# xmega_revC.net
KiCad netlist of a schematic drawn in EAGLE
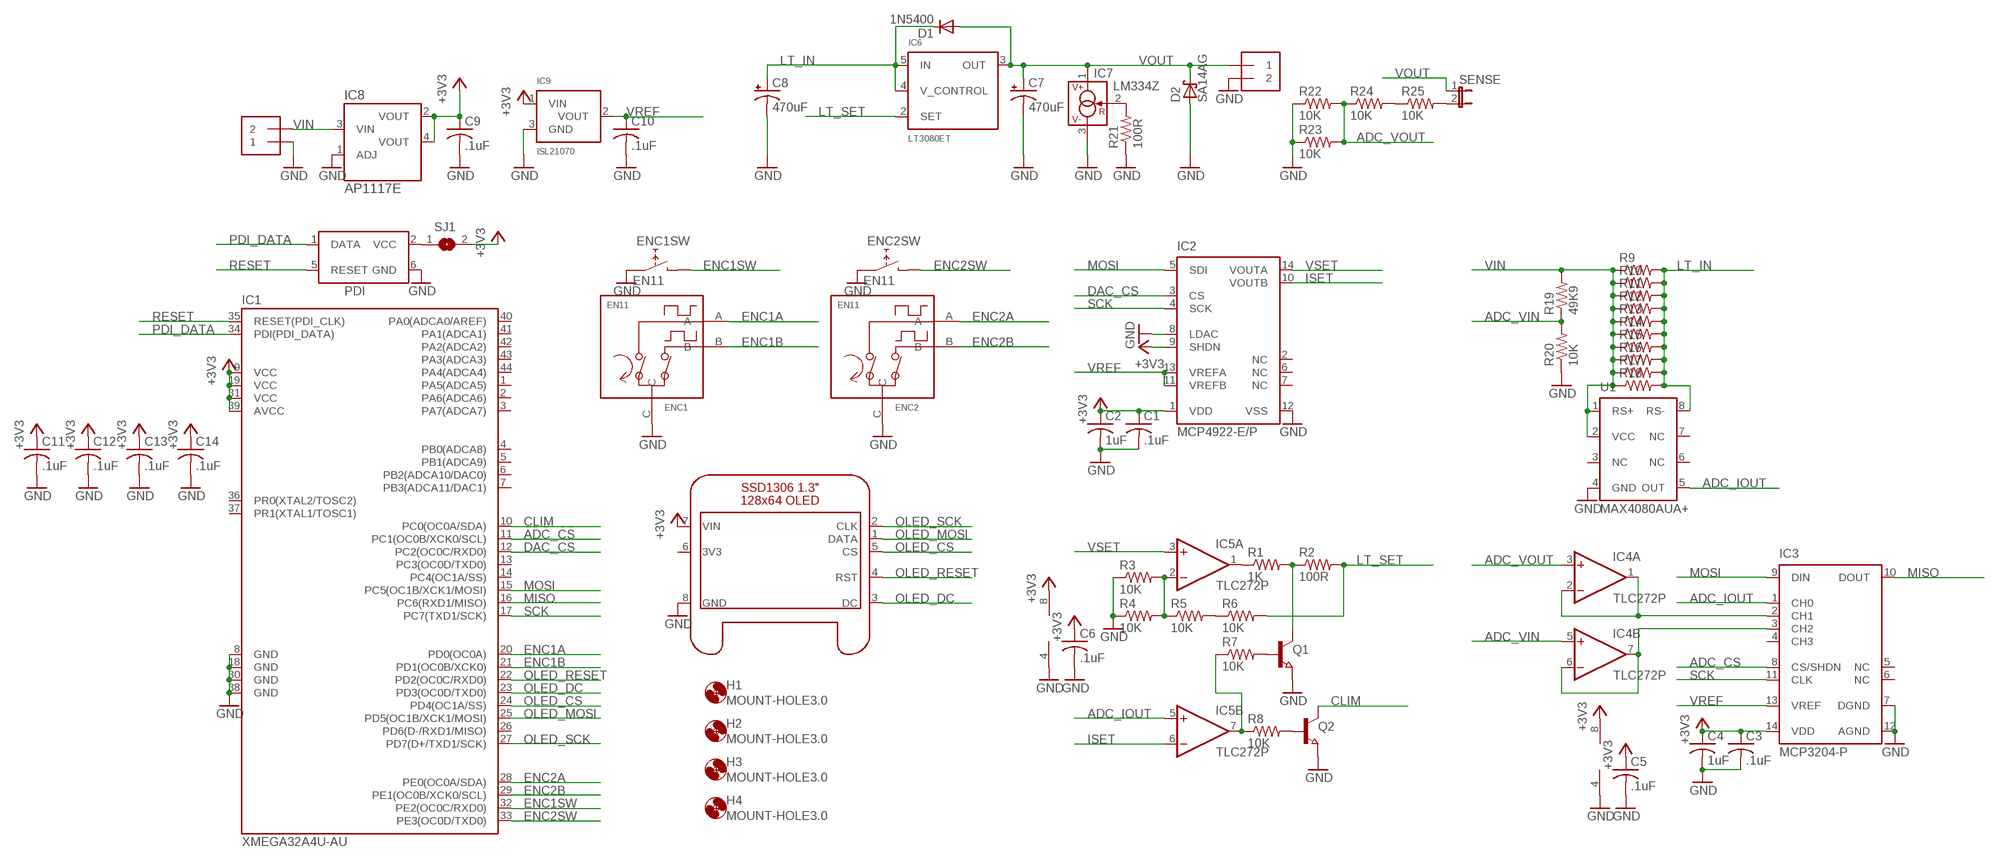
[diagram p0: schematic, sheet 1]

(export (version "E")
  (design (tool "Eeschema 10.0.6"))
  (components
    (comp (ref "C1")
      (value ".1uF")
      (footprint "eagle-import:C050-024X044")
      (libsource (lib "eagle-import") (part "C-US050-024X044"))
    )
    (comp (ref "C2")
      (value "1uF")
      (footprint "eagle-import:C050-024X044")
      (libsource (lib "eagle-import") (part "C-US050-024X044"))
    )
    (comp (ref "C3")
      (value ".1uF")
      (footprint "eagle-import:C050-024X044")
      (libsource (lib "eagle-import") (part "C-US050-024X044"))
    )
    (comp (ref "C4")
      (value "1uF")
      (footprint "eagle-import:C050-024X044")
      (libsource (lib "eagle-import") (part "C-US050-024X044"))
    )
    (comp (ref "C5")
      (value ".1uF")
      (footprint "eagle-import:C050-024X044")
      (libsource (lib "eagle-import") (part "C-US050-024X044"))
    )
    (comp (ref "C6")
      (value ".1uF")
      (footprint "eagle-import:C050-024X044")
      (libsource (lib "eagle-import") (part "C-US050-024X044"))
    )
    (comp (ref "C7")
      (value "470uF")
      (footprint "eagle-import:E5-10,5")
      (libsource (lib "eagle-import") (part "CPOL-USE5-10.5"))
    )
    (comp (ref "C8")
      (value "470uF")
      (footprint "eagle-import:E5-10,5")
      (libsource (lib "eagle-import") (part "CPOL-USE5-10.5"))
    )
    (comp (ref "C9")
      (value ".1uF")
      (footprint "eagle-import:C050-024X044")
      (libsource (lib "eagle-import") (part "C-US050-024X044"))
    )
    (comp (ref "C10")
      (value ".1uF")
      (footprint "eagle-import:C050-024X044")
      (libsource (lib "eagle-import") (part "C-US050-024X044"))
    )
    (comp (ref "C11")
      (value ".1uF")
      (footprint "eagle-import:C0805K")
      (libsource (lib "eagle-import") (part "C-USC0805K"))
    )
    (comp (ref "C12")
      (value ".1uF")
      (footprint "eagle-import:C0805K")
      (libsource (lib "eagle-import") (part "C-USC0805K"))
    )
    (comp (ref "C13")
      (value ".1uF")
      (footprint "eagle-import:C0805K")
      (libsource (lib "eagle-import") (part "C-USC0805K"))
    )
    (comp (ref "C14")
      (value ".1uF")
      (footprint "eagle-import:C0805K")
      (libsource (lib "eagle-import") (part "C-USC0805K"))
    )
    (comp (ref "D1")
      (value "1N5400")
      (footprint "eagle-import:DO201-15")
      (libsource (lib "eagle-import") (part "1N5400"))
    )
    (comp (ref "D2")
      (value "SA14AG")
      (footprint "eagle-import:DO41-7")
      (libsource (lib "eagle-import") (part "SCHOTTKY-DIODEDO41-7"))
    )
    (comp (ref "ENC1")
      (value "EN11")
      (footprint "eagle-import:EN11-VS_")
      (libsource (lib "eagle-import") (part "EN11"))
    )
    (comp (ref "ENC2")
      (value "EN11")
      (footprint "eagle-import:EN11-VS_")
      (libsource (lib "eagle-import") (part "EN11"))
    )
    (comp (ref "H1")
      (value "MOUNT-HOLE3.0")
      (footprint "eagle-import:3,0")
      (libsource (lib "eagle-import") (part "MOUNT-HOLE3.0"))
    )
    (comp (ref "H2")
      (value "MOUNT-HOLE3.0")
      (footprint "eagle-import:3,0")
      (libsource (lib "eagle-import") (part "MOUNT-HOLE3.0"))
    )
    (comp (ref "H3")
      (value "MOUNT-HOLE3.0")
      (footprint "eagle-import:3,0")
      (libsource (lib "eagle-import") (part "MOUNT-HOLE3.0"))
    )
    (comp (ref "H4")
      (value "MOUNT-HOLE3.0")
      (footprint "eagle-import:3,0")
      (libsource (lib "eagle-import") (part "MOUNT-HOLE3.0"))
    )
    (comp (ref "IC1")
      (value "XMEGA32A4U-AU")
      (footprint "eagle-import:TQFP44")
      (libsource (lib "eagle-import") (part "XMEGA32A4U-AU"))
    )
    (comp (ref "IC2")
      (value "MCP4922-E/P")
      (footprint "eagle-import:DIL14")
      (libsource (lib "eagle-import") (part "MCP4922-E/P"))
    )
    (comp (ref "IC3")
      (value "MCP3204-P")
      (footprint "eagle-import:DIL14")
      (libsource (lib "eagle-import") (part "MCP3204-P"))
    )
    (comp (ref "IC4")
      (value "TLC272P")
      (footprint "eagle-import:DIL08")
      (libsource (lib "eagle-import") (part "TLC272P"))
    )
    (comp (ref "IC5")
      (value "TLC272P")
      (footprint "eagle-import:DIL08")
      (libsource (lib "eagle-import") (part "TLC272P"))
    )
    (comp (ref "IC6")
      (value "LT3080ET")
      (footprint "eagle-import:TO220-51")
      (libsource (lib "eagle-import") (part "LT3080ET"))
    )
    (comp (ref "IC7")
      (value "LM334Z")
      (footprint "eagle-import:TO92")
      (libsource (lib "eagle-import") (part "LM34Z3"))
    )
    (comp (ref "IC8")
      (value "AP1117E")
      (footprint "eagle-import:SOT223-3")
      (libsource (lib "eagle-import") (part "AP1117E"))
    )
    (comp (ref "IC9")
      (value "ISL21070")
      (footprint "eagle-import:SOT-23")
      (libsource (lib "eagle-import") (part "ISL21070"))
    )
    (comp (ref "OLED1")
      (value "128X64_OLED")
      (footprint "eagle-import:128X64_OLED")
      (libsource (lib "eagle-import") (part "128X64_OLED"))
    )
    (comp (ref "OUT")
      (value "1X2-3.5MM")
      (footprint "eagle-import:1X2-3.5MM")
      (libsource (lib "eagle-import") (part "1X2-3.5MM"))
    )
    (comp (ref "PDI")
      (value "XMEGAPDI")
      (footprint "eagle-import:AVRISP")
      (libsource (lib "eagle-import") (part "XMEGAPDI"))
    )
    (comp (ref "Q1")
      (value "NPN-TRANSISTOR_SOT23")
      (footprint "eagle-import:SOT23")
      (libsource (lib "eagle-import") (part "NPN-TRANSISTOR_SOT23"))
    )
    (comp (ref "Q2")
      (value "NPN-TRANSISTOR_SOT23")
      (footprint "eagle-import:SOT23")
      (libsource (lib "eagle-import") (part "NPN-TRANSISTOR_SOT23"))
    )
    (comp (ref "R1")
      (value "1K")
      (footprint "eagle-import:R0805")
      (libsource (lib "eagle-import") (part "R-US_R0805"))
    )
    (comp (ref "R2")
      (value "100R")
      (footprint "eagle-import:R0805")
      (libsource (lib "eagle-import") (part "R-US_R0805"))
    )
    (comp (ref "R3")
      (value "10K")
      (footprint "eagle-import:R0805")
      (libsource (lib "eagle-import") (part "R-US_R0805"))
    )
    (comp (ref "R4")
      (value "10K")
      (footprint "eagle-import:R0805")
      (libsource (lib "eagle-import") (part "R-US_R0805"))
    )
    (comp (ref "R5")
      (value "10K")
      (footprint "eagle-import:R0805")
      (libsource (lib "eagle-import") (part "R-US_R0805"))
    )
    (comp (ref "R6")
      (value "10K")
      (footprint "eagle-import:R0805")
      (libsource (lib "eagle-import") (part "R-US_R0805"))
    )
    (comp (ref "R7")
      (value "10K")
      (footprint "eagle-import:R0805")
      (libsource (lib "eagle-import") (part "R-US_R0805"))
    )
    (comp (ref "R8")
      (value "10K")
      (footprint "eagle-import:R0805")
      (libsource (lib "eagle-import") (part "R-US_R0805"))
    )
    (comp (ref "R9")
      (value "R-US_0207/10")
      (footprint "eagle-import:0207_10")
      (libsource (lib "eagle-import") (part "R-US_0207/10"))
    )
    (comp (ref "R10")
      (value "R-US_0207/10")
      (footprint "eagle-import:0207_10")
      (libsource (lib "eagle-import") (part "R-US_0207/10"))
    )
    (comp (ref "R11")
      (value "R-US_0207/10")
      (footprint "eagle-import:0207_10")
      (libsource (lib "eagle-import") (part "R-US_0207/10"))
    )
    (comp (ref "R12")
      (value "R-US_0207/10")
      (footprint "eagle-import:0207_10")
      (libsource (lib "eagle-import") (part "R-US_0207/10"))
    )
    (comp (ref "R13")
      (value "R-US_0207/10")
      (footprint "eagle-import:0207_10")
      (libsource (lib "eagle-import") (part "R-US_0207/10"))
    )
    (comp (ref "R14")
      (value "R-US_0207/10")
      (footprint "eagle-import:0207_10")
      (libsource (lib "eagle-import") (part "R-US_0207/10"))
    )
    (comp (ref "R15")
      (value "R-US_0207/10")
      (footprint "eagle-import:0207_10")
      (libsource (lib "eagle-import") (part "R-US_0207/10"))
    )
    (comp (ref "R16")
      (value "R-US_0207/10")
      (footprint "eagle-import:0207_10")
      (libsource (lib "eagle-import") (part "R-US_0207/10"))
    )
    (comp (ref "R17")
      (value "R-US_0207/10")
      (footprint "eagle-import:0207_10")
      (libsource (lib "eagle-import") (part "R-US_0207/10"))
    )
    (comp (ref "R18")
      (value "R-US_0207/10")
      (footprint "eagle-import:0207_10")
      (libsource (lib "eagle-import") (part "R-US_0207/10"))
    )
    (comp (ref "R19")
      (value "49K9")
      (footprint "eagle-import:R0805")
      (libsource (lib "eagle-import") (part "R-US_R0805"))
    )
    (comp (ref "R20")
      (value "10K")
      (footprint "eagle-import:R0805")
      (libsource (lib "eagle-import") (part "R-US_R0805"))
    )
    (comp (ref "R21")
      (value "100R")
      (footprint "eagle-import:R0805")
      (libsource (lib "eagle-import") (part "R-US_R0805"))
    )
    (comp (ref "R22")
      (value "10K")
      (footprint "eagle-import:R0805")
      (libsource (lib "eagle-import") (part "R-US_R0805"))
    )
    (comp (ref "R23")
      (value "10K")
      (footprint "eagle-import:R0805")
      (libsource (lib "eagle-import") (part "R-US_R0805"))
    )
    (comp (ref "R24")
      (value "10K")
      (footprint "eagle-import:R0805")
      (libsource (lib "eagle-import") (part "R-US_R0805"))
    )
    (comp (ref "R25")
      (value "10K")
      (footprint "eagle-import:R0805")
      (libsource (lib "eagle-import") (part "R-US_R0805"))
    )
    (comp (ref "SENSE")
      (value "JP1E")
      (footprint "eagle-import:JP1")
      (libsource (lib "eagle-import") (part "JP1E"))
    )
    (comp (ref "SJ1") (value "SJ") (footprint "eagle-import:SJ") (libsource (lib "eagle-import") (part "SJ")))
    (comp (ref "U1")
      (value "MAX4080AUA+")
      (footprint "eagle-import:SO08")
      (libsource (lib "eagle-import") (part "MAX4080AUA+"))
    )
    (comp (ref "VIN")
      (value "1X2-3.5MM")
      (footprint "eagle-import:1X2-3.5MM")
      (libsource (lib "eagle-import") (part "1X2-3.5MM"))
    )
  )
  (nets
    (net (code "1") (name "+3V3") (class "Default")
      (node (ref "C1") (pin "1") (pinfunction "1_1") (pintype "passive"))
      (node (ref "C11") (pin "1") (pinfunction "1_1") (pintype "passive"))
      (node (ref "C12") (pin "1") (pinfunction "1_1") (pintype "passive"))
      (node (ref "C13") (pin "1") (pinfunction "1_1") (pintype "passive"))
      (node (ref "C14") (pin "1") (pinfunction "1_1") (pintype "passive"))
      (node (ref "C2") (pin "1") (pinfunction "1_1") (pintype "passive"))
      (node (ref "C3") (pin "1") (pinfunction "1_1") (pintype "passive"))
      (node (ref "C4") (pin "1") (pinfunction "1_1") (pintype "passive"))
      (node (ref "C5") (pin "1") (pinfunction "1_1") (pintype "passive"))
      (node (ref "C6") (pin "1") (pinfunction "1_1") (pintype "passive"))
      (node (ref "C9") (pin "1") (pinfunction "1_1") (pintype "passive"))
      (node (ref "IC1") (pin "19") (pinfunction "VCC_19") (pintype "power_in"))
      (node (ref "IC1") (pin "31") (pinfunction "VCC_31") (pintype "power_in"))
      (node (ref "IC1") (pin "39") (pinfunction "AVCC_39") (pintype "power_in"))
      (node (ref "IC1") (pin "9") (pinfunction "VCC_9") (pintype "power_in"))
      (node (ref "IC2") (pin "1") (pinfunction "VDD_1") (pintype "bidirectional"))
      (node (ref "IC2") (pin "9") (pinfunction "SHDN_9") (pintype "bidirectional"))
      (node (ref "IC3") (pin "14") (pinfunction "VDD_14") (pintype "bidirectional"))
      (node (ref "IC4") (pin "8") (pinfunction "V+_8") (pintype "power_in"))
      (node (ref "IC5") (pin "8") (pinfunction "V+_8") (pintype "power_in"))
      (node (ref "IC8") (pin "2") (pinfunction "VOUT_2") (pintype "bidirectional"))
      (node (ref "IC8") (pin "4") (pinfunction "VOUT_4") (pintype "bidirectional"))
      (node (ref "IC9") (pin "1") (pinfunction "VIN_1") (pintype "bidirectional"))
      (node (ref "OLED1") (pin "7") (pinfunction "VIN_7") (pintype "power_in"))
      (node (ref "SJ1") (pin "2") (pinfunction "2_2") (pintype "passive"))
    )
    (net (code "2") (name "/3V3") (class "Default")
      (node (ref "OLED1") (pin "6") (pinfunction "3V3_6") (pintype "power_in"))
    )
    (net (code "3") (name "/ADC_CS") (class "Default")
      (node (ref "IC1") (pin "11") (pinfunction "PC1(OC0B/XCK0/SCL)_11") (pintype "bidirectional"))
      (node (ref "IC3") (pin "8") (pinfunction "CS/SHDN_8") (pintype "bidirectional"))
    )
    (net (code "4") (name "/ADC_IOUT") (class "Default")
      (node (ref "IC3") (pin "1") (pinfunction "CH0_1") (pintype "bidirectional"))
      (node (ref "IC5") (pin "5") (pinfunction "+IN_5") (pintype "input"))
      (node (ref "U1") (pin "5") (pinfunction "OUT_5") (pintype "bidirectional"))
    )
    (net (code "5") (name "/ADC_VIN") (class "Default")
      (node (ref "IC4") (pin "5") (pinfunction "+IN_5") (pintype "input"))
      (node (ref "R19") (pin "1") (pinfunction "1_1") (pintype "passive"))
      (node (ref "R20") (pin "2") (pinfunction "2_2") (pintype "passive"))
    )
    (net (code "6") (name "/ADC_VOUT") (class "Default")
      (node (ref "IC4") (pin "3") (pinfunction "+IN_3") (pintype "input"))
      (node (ref "R22") (pin "2") (pinfunction "2_2") (pintype "passive"))
      (node (ref "R23") (pin "2") (pinfunction "2_2") (pintype "passive"))
      (node (ref "R24") (pin "1") (pinfunction "1_1") (pintype "passive"))
    )
    (net (code "7") (name "/CLIM") (class "Default")
      (node (ref "IC1") (pin "10") (pinfunction "PC0(OC0A/SDA)_10") (pintype "bidirectional"))
      (node (ref "Q2") (pin "3") (pinfunction "C_3") (pintype "passive"))
    )
    (net (code "8") (name "/DAC_CS") (class "Default")
      (node (ref "IC1") (pin "12") (pinfunction "PC2(OC0C/RXD0)_12") (pintype "bidirectional"))
      (node (ref "IC2") (pin "3") (pinfunction "CS_3") (pintype "bidirectional"))
    )
    (net (code "9") (name "/ENC1A") (class "Default")
      (node (ref "ENC1") (pin "A") (pinfunction "A_A") (pintype "bidirectional"))
      (node (ref "IC1") (pin "20") (pinfunction "PD0(OC0A)_20") (pintype "bidirectional"))
    )
    (net (code "10") (name "/ENC1B") (class "Default")
      (node (ref "ENC1") (pin "B") (pinfunction "B_B") (pintype "bidirectional"))
      (node (ref "IC1") (pin "21") (pinfunction "PD1(OC0B/XCK0)_21") (pintype "bidirectional"))
    )
    (net (code "11") (name "/ENC1SW") (class "Default")
      (node (ref "ENC1") (pin "E") (pinfunction "E_E") (pintype "passive"))
      (node (ref "IC1") (pin "32") (pinfunction "PE2(OC0C/RXD0)_32") (pintype "bidirectional"))
    )
    (net (code "12") (name "/ENC2A") (class "Default")
      (node (ref "ENC2") (pin "A") (pinfunction "A_A") (pintype "bidirectional"))
      (node (ref "IC1") (pin "28") (pinfunction "PE0(OC0A/SDA)_28") (pintype "bidirectional"))
    )
    (net (code "13") (name "/ENC2B") (class "Default")
      (node (ref "ENC2") (pin "B") (pinfunction "B_B") (pintype "bidirectional"))
      (node (ref "IC1") (pin "29") (pinfunction "PE1(OC0B/XCK0/SCL)_29") (pintype "bidirectional"))
    )
    (net (code "14") (name "/ENC2SW") (class "Default")
      (node (ref "ENC2") (pin "E") (pinfunction "E_E") (pintype "passive"))
      (node (ref "IC1") (pin "33") (pinfunction "PE3(OC0D/TXD0)_33") (pintype "bidirectional"))
    )
    (net (code "15") (name "/ISET") (class "Default")
      (node (ref "IC2") (pin "10") (pinfunction "VOUTB_10") (pintype "bidirectional"))
      (node (ref "IC5") (pin "6") (pinfunction "-IN_6") (pintype "input"))
    )
    (net (code "16") (name "/LT_IN") (class "Default")
      (node (ref "C8") (pin "+") (pinfunction "+_+") (pintype "passive"))
      (node (ref "D1") (pin "C") (pinfunction "C_C") (pintype "passive"))
      (node (ref "IC6") (pin "4") (pinfunction "V_CONTROL_4") (pintype "bidirectional"))
      (node (ref "IC6") (pin "5") (pinfunction "IN_5") (pintype "bidirectional"))
      (node (ref "R10") (pin "2") (pinfunction "2_2") (pintype "passive"))
      (node (ref "R11") (pin "2") (pinfunction "2_2") (pintype "passive"))
      (node (ref "R12") (pin "2") (pinfunction "2_2") (pintype "passive"))
      (node (ref "R13") (pin "2") (pinfunction "2_2") (pintype "passive"))
      (node (ref "R14") (pin "2") (pinfunction "2_2") (pintype "passive"))
      (node (ref "R15") (pin "2") (pinfunction "2_2") (pintype "passive"))
      (node (ref "R16") (pin "2") (pinfunction "2_2") (pintype "passive"))
      (node (ref "R17") (pin "2") (pinfunction "2_2") (pintype "passive"))
      (node (ref "R18") (pin "2") (pinfunction "2_2") (pintype "passive"))
      (node (ref "R9") (pin "2") (pinfunction "2_2") (pintype "passive"))
      (node (ref "U1") (pin "8") (pinfunction "RS-_8") (pintype "bidirectional"))
    )
    (net (code "17") (name "/LT_SET") (class "Default")
      (node (ref "IC6") (pin "2") (pinfunction "SET_2") (pintype "bidirectional"))
      (node (ref "R2") (pin "2") (pinfunction "2_2") (pintype "passive"))
      (node (ref "R6") (pin "2") (pinfunction "2_2") (pintype "passive"))
    )
    (net (code "18") (name "/MISO") (class "Default")
      (node (ref "IC1") (pin "16") (pinfunction "PC6(RXD1/MISO)_16") (pintype "bidirectional"))
      (node (ref "IC3") (pin "10") (pinfunction "DOUT_10") (pintype "bidirectional"))
    )
    (net (code "19") (name "/MOSI") (class "Default")
      (node (ref "IC1") (pin "15") (pinfunction "PC5(OC1B/XCK1/MOSI)_15") (pintype "bidirectional"))
      (node (ref "IC2") (pin "5") (pinfunction "SDI_5") (pintype "bidirectional"))
      (node (ref "IC3") (pin "9") (pinfunction "DIN_9") (pintype "bidirectional"))
    )
    (net (code "20") (name "/OLED_CS") (class "Default")
      (node (ref "IC1") (pin "24") (pinfunction "PD4(OC1A/SS)_24") (pintype "bidirectional"))
      (node (ref "OLED1") (pin "5") (pinfunction "CS_5") (pintype "input"))
    )
    (net (code "21") (name "/OLED_DC") (class "Default")
      (node (ref "IC1") (pin "23") (pinfunction "PD3(OC0D/TXD0)_23") (pintype "bidirectional"))
      (node (ref "OLED1") (pin "3") (pinfunction "DC_3") (pintype "input"))
    )
    (net (code "22") (name "/OLED_MOSI") (class "Default")
      (node (ref "IC1") (pin "25") (pinfunction "PD5(OC1B/XCK1/MOSI)_25") (pintype "bidirectional"))
      (node (ref "OLED1") (pin "1") (pinfunction "DATA_1") (pintype "input"))
    )
    (net (code "23") (name "/OLED_RESET") (class "Default")
      (node (ref "IC1") (pin "22") (pinfunction "PD2(OC0C/RXD0)_22") (pintype "bidirectional"))
      (node (ref "OLED1") (pin "4") (pinfunction "RST_4") (pintype "input"))
    )
    (net (code "24") (name "/OLED_SCK") (class "Default")
      (node (ref "IC1") (pin "27") (pinfunction "PD7(D+/TXD1/SCK)_27") (pintype "bidirectional"))
      (node (ref "OLED1") (pin "2") (pinfunction "CLK_2") (pintype "input"))
    )
    (net (code "25") (name "/PDI_DATA") (class "Default")
      (node (ref "IC1") (pin "34") (pinfunction "PDI(PDI_DATA)_34") (pintype "bidirectional"))
      (node (ref "PDI") (pin "1") (pinfunction "DATA_1") (pintype "input"))
    )
    (net (code "26") (name "/RESET") (class "Default")
      (node (ref "IC1") (pin "35") (pinfunction "RESET(PDI_CLK)_35") (pintype "input"))
      (node (ref "PDI") (pin "5") (pinfunction "RESET_5") (pintype "output"))
    )
    (net (code "27") (name "/SCK") (class "Default")
      (node (ref "IC1") (pin "17") (pinfunction "PC7(TXD1/SCK)_17") (pintype "bidirectional"))
      (node (ref "IC2") (pin "4") (pinfunction "SCK_4") (pintype "bidirectional"))
      (node (ref "IC3") (pin "11") (pinfunction "CLK_11") (pintype "bidirectional"))
    )
    (net (code "28") (name "/VIN") (class "Default")
      (node (ref "IC8") (pin "3") (pinfunction "VIN_3") (pintype "bidirectional"))
      (node (ref "R10") (pin "1") (pinfunction "1_1") (pintype "passive"))
      (node (ref "R11") (pin "1") (pinfunction "1_1") (pintype "passive"))
      (node (ref "R12") (pin "1") (pinfunction "1_1") (pintype "passive"))
      (node (ref "R13") (pin "1") (pinfunction "1_1") (pintype "passive"))
      (node (ref "R14") (pin "1") (pinfunction "1_1") (pintype "passive"))
      (node (ref "R15") (pin "1") (pinfunction "1_1") (pintype "passive"))
      (node (ref "R16") (pin "1") (pinfunction "1_1") (pintype "passive"))
      (node (ref "R17") (pin "1") (pinfunction "1_1") (pintype "passive"))
      (node (ref "R18") (pin "1") (pinfunction "1_1") (pintype "passive"))
      (node (ref "R19") (pin "2") (pinfunction "2_2") (pintype "passive"))
      (node (ref "R9") (pin "1") (pinfunction "1_1") (pintype "passive"))
      (node (ref "U1") (pin "1") (pinfunction "RS+_1") (pintype "bidirectional"))
      (node (ref "U1") (pin "2") (pinfunction "VCC_2") (pintype "bidirectional"))
      (node (ref "VIN") (pin "2") (pinfunction "2_2") (pintype "passive"))
    )
    (net (code "29") (name "/VOUT") (class "Default")
      (node (ref "C7") (pin "+") (pinfunction "+_+") (pintype "passive"))
      (node (ref "D1") (pin "A") (pinfunction "A_A") (pintype "passive"))
      (node (ref "D2") (pin "C") (pinfunction "C_C") (pintype "passive"))
      (node (ref "IC6") (pin "3") (pinfunction "OUT_3") (pintype "bidirectional"))
      (node (ref "IC7") (pin "1") (pinfunction "V+_1") (pintype "passive"))
      (node (ref "OUT") (pin "1") (pinfunction "1_1") (pintype "passive"))
      (node (ref "SENSE") (pin "1") (pinfunction "1_1") (pintype "passive"))
    )
    (net (code "30") (name "/VREF") (class "Default")
      (node (ref "C10") (pin "1") (pinfunction "1_1") (pintype "passive"))
      (node (ref "IC2") (pin "11") (pinfunction "VREFB_11") (pintype "bidirectional"))
      (node (ref "IC2") (pin "13") (pinfunction "VREFA_13") (pintype "bidirectional"))
      (node (ref "IC3") (pin "13") (pinfunction "VREF_13") (pintype "bidirectional"))
      (node (ref "IC9") (pin "2") (pinfunction "VOUT_2") (pintype "bidirectional"))
    )
    (net (code "31") (name "/VSET") (class "Default")
      (node (ref "IC2") (pin "14") (pinfunction "VOUTA_14") (pintype "bidirectional"))
      (node (ref "IC5") (pin "3") (pinfunction "+IN_3") (pintype "input"))
    )
    (net (code "32") (name "GND") (class "Default")
      (node (ref "C1") (pin "2") (pinfunction "2_2") (pintype "passive"))
      (node (ref "C10") (pin "2") (pinfunction "2_2") (pintype "passive"))
      (node (ref "C11") (pin "2") (pinfunction "2_2") (pintype "passive"))
      (node (ref "C12") (pin "2") (pinfunction "2_2") (pintype "passive"))
      (node (ref "C13") (pin "2") (pinfunction "2_2") (pintype "passive"))
      (node (ref "C14") (pin "2") (pinfunction "2_2") (pintype "passive"))
      (node (ref "C2") (pin "2") (pinfunction "2_2") (pintype "passive"))
      (node (ref "C3") (pin "2") (pinfunction "2_2") (pintype "passive"))
      (node (ref "C4") (pin "2") (pinfunction "2_2") (pintype "passive"))
      (node (ref "C5") (pin "2") (pinfunction "2_2") (pintype "passive"))
      (node (ref "C6") (pin "2") (pinfunction "2_2") (pintype "passive"))
      (node (ref "C7") (pin "-") (pinfunction "-_-") (pintype "passive"))
      (node (ref "C8") (pin "-") (pinfunction "-_-") (pintype "passive"))
      (node (ref "C9") (pin "2") (pinfunction "2_2") (pintype "passive"))
      (node (ref "D2") (pin "A") (pinfunction "A_A") (pintype "passive"))
      (node (ref "ENC1") (pin "C") (pinfunction "C_C") (pintype "bidirectional"))
      (node (ref "ENC1") (pin "D") (pinfunction "D_D") (pintype "passive"))
      (node (ref "ENC2") (pin "C") (pinfunction "C_C") (pintype "bidirectional"))
      (node (ref "ENC2") (pin "D") (pinfunction "D_D") (pintype "passive"))
      (node (ref "IC1") (pin "18") (pinfunction "GND_18") (pintype "power_in"))
      (node (ref "IC1") (pin "30") (pinfunction "GND_30") (pintype "power_in"))
      (node (ref "IC1") (pin "38") (pinfunction "GND_38") (pintype "power_in"))
      (node (ref "IC1") (pin "8") (pinfunction "GND_8") (pintype "power_in"))
      (node (ref "IC2") (pin "12") (pinfunction "VSS_12") (pintype "bidirectional"))
      (node (ref "IC2") (pin "8") (pinfunction "LDAC_8") (pintype "bidirectional"))
      (node (ref "IC3") (pin "12") (pinfunction "AGND_12") (pintype "bidirectional"))
      (node (ref "IC3") (pin "7") (pinfunction "DGND_7") (pintype "bidirectional"))
      (node (ref "IC4") (pin "4") (pinfunction "V-_4") (pintype "power_in"))
      (node (ref "IC5") (pin "4") (pinfunction "V-_4") (pintype "power_in"))
      (node (ref "IC7") (pin "3") (pinfunction "V-_3") (pintype "passive"))
      (node (ref "IC8") (pin "1") (pinfunction "ADJ_1") (pintype "bidirectional"))
      (node (ref "IC9") (pin "3") (pinfunction "GND_3") (pintype "bidirectional"))
      (node (ref "OLED1") (pin "8") (pinfunction "GND_8") (pintype "power_in"))
      (node (ref "OUT") (pin "2") (pinfunction "2_2") (pintype "passive"))
      (node (ref "PDI") (pin "6") (pinfunction "GND_6") (pintype "power_in"))
      (node (ref "Q1") (pin "2") (pinfunction "E_2") (pintype "passive"))
      (node (ref "Q2") (pin "2") (pinfunction "E_2") (pintype "passive"))
      (node (ref "R20") (pin "1") (pinfunction "1_1") (pintype "passive"))
      (node (ref "R21") (pin "1") (pinfunction "1_1") (pintype "passive"))
      (node (ref "R22") (pin "1") (pinfunction "1_1") (pintype "passive"))
      (node (ref "R23") (pin "1") (pinfunction "1_1") (pintype "passive"))
      (node (ref "R3") (pin "1") (pinfunction "1_1") (pintype "passive"))
      (node (ref "R4") (pin "1") (pinfunction "1_1") (pintype "passive"))
      (node (ref "U1") (pin "4") (pinfunction "GND_4") (pintype "bidirectional"))
      (node (ref "VIN") (pin "1") (pinfunction "1_1") (pintype "passive"))
    )
    (net (code "33") (name "Net-(IC3-CH1)") (class "Default")
      (node (ref "IC3") (pin "2") (pinfunction "CH1_2") (pintype "bidirectional"))
      (node (ref "IC4") (pin "1") (pinfunction "OUT_1") (pintype "output"))
      (node (ref "IC4") (pin "2") (pinfunction "-IN_2") (pintype "input"))
    )
    (net (code "34") (name "Net-(IC3-CH2)") (class "Default")
      (node (ref "IC3") (pin "3") (pinfunction "CH2_3") (pintype "bidirectional"))
      (node (ref "IC4") (pin "6") (pinfunction "-IN_6") (pintype "input"))
      (node (ref "IC4") (pin "7") (pinfunction "OUT_7") (pintype "output"))
    )
    (net (code "35") (name "Net-(IC5A--IN)") (class "Default")
      (node (ref "IC5") (pin "2") (pinfunction "-IN_2") (pintype "input"))
      (node (ref "R3") (pin "2") (pinfunction "2_2") (pintype "passive"))
      (node (ref "R4") (pin "2") (pinfunction "2_2") (pintype "passive"))
      (node (ref "R5") (pin "1") (pinfunction "1_1") (pintype "passive"))
    )
    (net (code "36") (name "Net-(IC5A-OUT)") (class "Default")
      (node (ref "IC5") (pin "1") (pinfunction "OUT_1") (pintype "output"))
      (node (ref "R1") (pin "1") (pinfunction "1_1") (pintype "passive"))
    )
    (net (code "37") (name "Net-(IC5B-OUT)") (class "Default")
      (node (ref "IC5") (pin "7") (pinfunction "OUT_7") (pintype "output"))
      (node (ref "R7") (pin "1") (pinfunction "1_1") (pintype "passive"))
      (node (ref "R8") (pin "1") (pinfunction "1_1") (pintype "passive"))
    )
    (net (code "38") (name "Net-(IC7-R)") (class "Default")
      (node (ref "IC7") (pin "2") (pinfunction "R_2") (pintype "passive"))
      (node (ref "R21") (pin "2") (pinfunction "2_2") (pintype "passive"))
    )
    (net (code "39") (name "Net-(PDI-VCC)") (class "Default")
      (node (ref "PDI") (pin "2") (pinfunction "VCC_2") (pintype "power_in"))
      (node (ref "SJ1") (pin "1") (pinfunction "1_1") (pintype "passive"))
    )
    (net (code "40") (name "Net-(Q1-B)") (class "Default")
      (node (ref "Q1") (pin "1") (pinfunction "B_1") (pintype "passive"))
      (node (ref "R7") (pin "2") (pinfunction "2_2") (pintype "passive"))
    )
    (net (code "41") (name "Net-(Q1-C)") (class "Default")
      (node (ref "Q1") (pin "3") (pinfunction "C_3") (pintype "passive"))
      (node (ref "R1") (pin "2") (pinfunction "2_2") (pintype "passive"))
      (node (ref "R2") (pin "1") (pinfunction "1_1") (pintype "passive"))
    )
    (net (code "42") (name "Net-(Q2-B)") (class "Default")
      (node (ref "Q2") (pin "1") (pinfunction "B_1") (pintype "passive"))
      (node (ref "R8") (pin "2") (pinfunction "2_2") (pintype "passive"))
    )
    (net (code "43") (name "Net-(R5-Pad2)") (class "Default")
      (node (ref "R5") (pin "2") (pinfunction "2_2") (pintype "passive"))
      (node (ref "R6") (pin "1") (pinfunction "1_1") (pintype "passive"))
    )
    (net (code "44") (name "Net-(R24-Pad2)") (class "Default")
      (node (ref "R24") (pin "2") (pinfunction "2_2") (pintype "passive"))
      (node (ref "R25") (pin "1") (pinfunction "1_1") (pintype "passive"))
    )
    (net (code "45") (name "Net-(R25-Pad2)") (class "Default")
      (node (ref "R25") (pin "2") (pinfunction "2_2") (pintype "passive"))
      (node (ref "SENSE") (pin "2") (pinfunction "2_2") (pintype "passive"))
    )
    (net (code "46") (name "unconnected-(IC1-PA0(ADCA0{slash}AREF)-Pad40)") (class "Default")
      (node (ref "IC1") (pin "40") (pinfunction "PA0(ADCA0/AREF)_40") (pintype "bidirectional"))
    )
    (net (code "47") (name "unconnected-(IC1-PA1(ADCA1)-Pad41)") (class "Default")
      (node (ref "IC1") (pin "41") (pinfunction "PA1(ADCA1)_41") (pintype "bidirectional"))
    )
    (net (code "48") (name "unconnected-(IC1-PA2(ADCA2)-Pad42)") (class "Default")
      (node (ref "IC1") (pin "42") (pinfunction "PA2(ADCA2)_42") (pintype "bidirectional"))
    )
    (net (code "49") (name "unconnected-(IC1-PA3(ADCA3)-Pad43)") (class "Default")
      (node (ref "IC1") (pin "43") (pinfunction "PA3(ADCA3)_43") (pintype "bidirectional"))
    )
    (net (code "50") (name "unconnected-(IC1-PA4(ADCA4)-Pad44)") (class "Default")
      (node (ref "IC1") (pin "44") (pinfunction "PA4(ADCA4)_44") (pintype "bidirectional"))
    )
    (net (code "51") (name "unconnected-(IC1-PA5(ADCA5)-Pad1)") (class "Default")
      (node (ref "IC1") (pin "1") (pinfunction "PA5(ADCA5)_1") (pintype "bidirectional"))
    )
    (net (code "52") (name "unconnected-(IC1-PA6(ADCA6)-Pad2)") (class "Default")
      (node (ref "IC1") (pin "2") (pinfunction "PA6(ADCA6)_2") (pintype "bidirectional"))
    )
    (net (code "53") (name "unconnected-(IC1-PA7(ADCA7)-Pad3)") (class "Default")
      (node (ref "IC1") (pin "3") (pinfunction "PA7(ADCA7)_3") (pintype "bidirectional"))
    )
    (net (code "54") (name "unconnected-(IC1-PB0(ADCA8)-Pad4)") (class "Default")
      (node (ref "IC1") (pin "4") (pinfunction "PB0(ADCA8)_4") (pintype "bidirectional"))
    )
    (net (code "55") (name "unconnected-(IC1-PB1(ADCA9)-Pad5)") (class "Default")
      (node (ref "IC1") (pin "5") (pinfunction "PB1(ADCA9)_5") (pintype "bidirectional"))
    )
    (net (code "56") (name "unconnected-(IC1-PB2(ADCA10{slash}DAC0)-Pad6)") (class "Default")
      (node (ref "IC1") (pin "6") (pinfunction "PB2(ADCA10/DAC0)_6") (pintype "bidirectional"))
    )
    (net (code "57") (name "unconnected-(IC1-PB3(ADCA11{slash}DAC1)-Pad7)") (class "Default")
      (node (ref "IC1") (pin "7") (pinfunction "PB3(ADCA11/DAC1)_7") (pintype "bidirectional"))
    )
    (net (code "58") (name "unconnected-(IC1-PC3(OC0D{slash}TXD0)-Pad13)") (class "Default")
      (node (ref "IC1") (pin "13") (pinfunction "PC3(OC0D/TXD0)_13") (pintype "bidirectional"))
    )
    (net (code "59") (name "unconnected-(IC1-PC4(OC1A{slash}SS)-Pad14)") (class "Default")
      (node (ref "IC1") (pin "14") (pinfunction "PC4(OC1A/SS)_14") (pintype "bidirectional"))
    )
    (net (code "60") (name "unconnected-(IC1-PD6(D-{slash}RXD1{slash}MISO)-Pad26)") (class "Default")
      (node (ref "IC1") (pin "26") (pinfunction "PD6(D-/RXD1/MISO)_26") (pintype "bidirectional"))
    )
    (net (code "61") (name "unconnected-(IC1-PR0(XTAL2{slash}TOSC2)-Pad36)") (class "Default")
      (node (ref "IC1") (pin "36") (pinfunction "PR0(XTAL2/TOSC2)_36") (pintype "bidirectional"))
    )
    (net (code "62") (name "unconnected-(IC1-PR1(XTAL1{slash}TOSC1)-Pad37)") (class "Default")
      (node (ref "IC1") (pin "37") (pinfunction "PR1(XTAL1/TOSC1)_37") (pintype "bidirectional"))
    )
    (net (code "63") (name "unconnected-(IC2-NC-Pad2)") (class "Default")
      (node (ref "IC2") (pin "2") (pinfunction "NC_2") (pintype "bidirectional"))
    )
    (net (code "64") (name "unconnected-(IC2-NC-Pad6)") (class "Default")
      (node (ref "IC2") (pin "6") (pinfunction "NC_6") (pintype "bidirectional"))
    )
    (net (code "65") (name "unconnected-(IC2-NC-Pad7)") (class "Default")
      (node (ref "IC2") (pin "7") (pinfunction "NC_7") (pintype "bidirectional"))
    )
    (net (code "66") (name "unconnected-(IC3-CH3-Pad4)") (class "Default")
      (node (ref "IC3") (pin "4") (pinfunction "CH3_4") (pintype "bidirectional"))
    )
    (net (code "67") (name "unconnected-(IC3-NC-Pad5)") (class "Default")
      (node (ref "IC3") (pin "5") (pinfunction "NC_5") (pintype "bidirectional"))
    )
    (net (code "68") (name "unconnected-(IC3-NC-Pad6)") (class "Default")
      (node (ref "IC3") (pin "6") (pinfunction "NC_6") (pintype "bidirectional"))
    )
    (net (code "69") (name "unconnected-(U1-NC-Pad3)") (class "Default")
      (node (ref "U1") (pin "3") (pinfunction "NC_3") (pintype "bidirectional"))
    )
    (net (code "70") (name "unconnected-(U1-NC-Pad6)") (class "Default")
      (node (ref "U1") (pin "6") (pinfunction "NC_6") (pintype "bidirectional"))
    )
    (net (code "71") (name "unconnected-(U1-NC-Pad7)") (class "Default")
      (node (ref "U1") (pin "7") (pinfunction "NC_7") (pintype "bidirectional"))
    )
  )
)
